# 7_Mosfets.net
KiCad netlist of a schematic drawn in Altium Designer
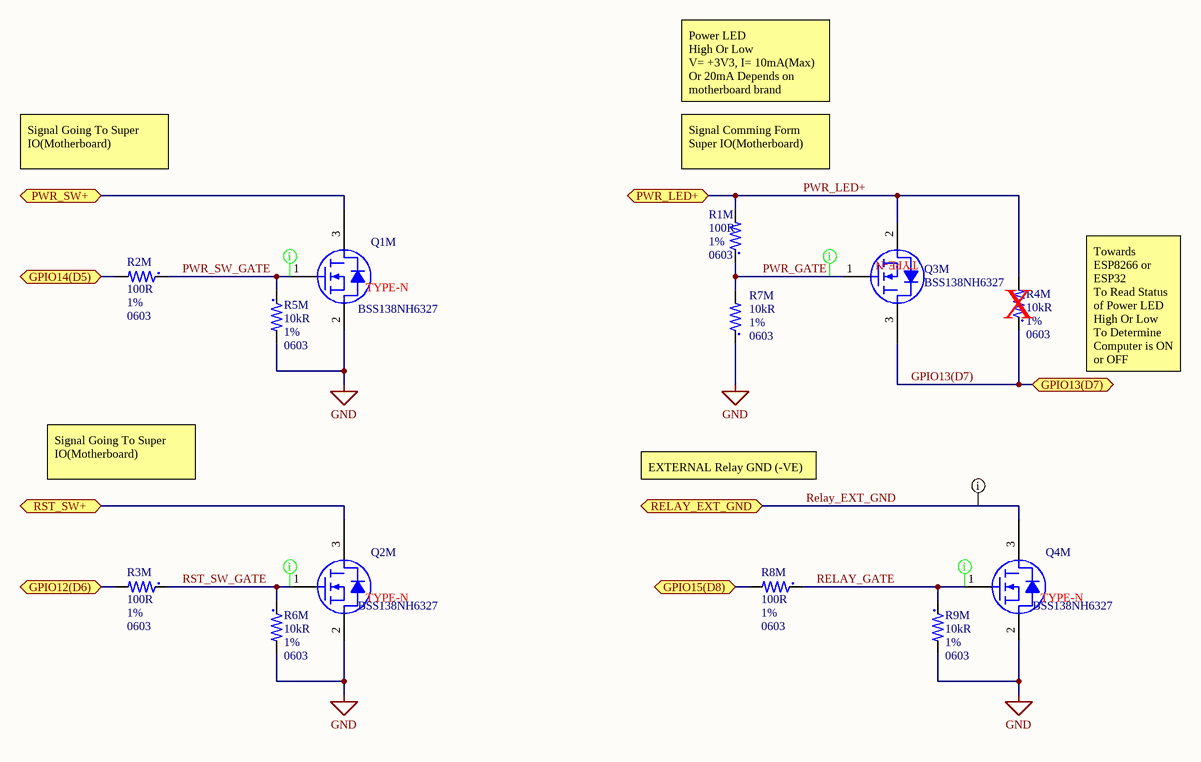
[diagram p0: 7_Mosfets.SchDoc]

(export (version "E")
  (design (tool "Eeschema 10.0.6"))
  (components
    (comp (ref "Q1M")
      (value "BSS138NH6327")
      (footprint "SOT-23-3-IPC_C")
      (description "Single N-Channel 60 V 3.5 Ohm 1 nC SIPMOS® Small Signal Mosfet - SOT-23")
      (fields (field (name "MANUFACTURER") "Infineon") (field (name "VOLTAGE") "50V"))
      (libsource (lib "") (part "BSS138NH6327_1"))
    )
    (comp (ref "Q2M")
      (value "BSS138NH6327")
      (footprint "SOT-23-3-IPC_C")
      (description "Single N-Channel 60 V 3.5 Ohm 1 nC SIPMOS® Small Signal Mosfet - SOT-23")
      (fields (field (name "MANUFACTURER") "Infineon") (field (name "VOLTAGE") "50V"))
      (libsource (lib "") (part "BSS138NH6327_1"))
    )
    (comp (ref "Q3M")
      (value "BSS138NH6327")
      (footprint "SOT-23-3-IPC_C")
      (description "Single N-Channel 60 V 3.5 Ohm 1 nC SIPMOS® Small Signal Mosfet - SOT-23")
      (fields (field (name "MANUFACTURER") "Infineon") (field (name "VOLTAGE") "50V"))
      (libsource (lib "Lib_Mosfet_NPN") (part "BSS138NH6327"))
    )
    (comp (ref "Q4M")
      (value "BSS138NH6327")
      (footprint "SOT-23-3-IPC_C")
      (description "Single N-Channel 60 V 3.5 Ohm 1 nC SIPMOS® Small Signal Mosfet - SOT-23")
      (fields (field (name "MANUFACTURER") "Infineon") (field (name "VOLTAGE") "50V"))
      (libsource (lib "") (part "BSS138NH6327_1"))
    )
    (comp (ref "R1M")
      (value "100R")
      (footprint "R0603-MFG")
      (description "SMD Chip Resistor, 100 Ohm, ± 1%, 100 mW, 0603 [1608 Metric], Thick Film, General Purpose")
      (fields
        (field (name "MANUFACTURER") "Yageo")
        (field (name "MANUFACTURER PART NUMBER") "AC0603FR-07100RL")
        (field (name "TOLERANCE") "1%")
        (field (name "CASE/PACKAGE") "0603")
      )
      (libsource (lib "Lib_Register_0603") (part "100R"))
    )
    (comp (ref "R2M")
      (value "100R")
      (footprint "R0603-MFG")
      (description "SMD Chip Resistor, 100 Ohm, ± 1%, 100 mW, 0603 [1608 Metric], Thick Film, General Purpose")
      (fields
        (field (name "MANUFACTURER") "Yageo")
        (field (name "MANUFACTURER PART NUMBER") "AC0603FR-07100RL")
        (field (name "TOLERANCE") "1%")
        (field (name "CASE/PACKAGE") "0603")
      )
      (libsource (lib "Lib_Register_0603") (part "100R"))
    )
    (comp (ref "R3M")
      (value "100R")
      (footprint "R0603-MFG")
      (description "SMD Chip Resistor, 100 Ohm, ± 1%, 100 mW, 0603 [1608 Metric], Thick Film, General Purpose")
      (fields
        (field (name "MANUFACTURER") "Yageo")
        (field (name "MANUFACTURER PART NUMBER") "AC0603FR-07100RL")
        (field (name "TOLERANCE") "1%")
        (field (name "CASE/PACKAGE") "0603")
      )
      (libsource (lib "Lib_Register_0603") (part "100R"))
    )
    (comp (ref "R4M")
      (value "10kR")
      (footprint "R0603-MFG")
      (description "SMD Chip Resistor, 10 kOhm, ± 1%, 100 mW, 0603 [1608 Metric], Thick Film, General Purpose")
      (fields
        (field (name "MANUFACTURER") "Yageo")
        (field (name "MANUFACTURER PART NUMBER") "RC0603FR-0710KL")
        (field (name "TOLERANCE") "1%")
        (field (name "CASE/PACKAGE") "0603")
      )
      (libsource (lib "Lib_Register_0603") (part "10K"))
    )
    (comp (ref "R5M")
      (value "10kR")
      (footprint "R0603-MFG")
      (description "SMD Chip Resistor, 10 kOhm, ± 1%, 100 mW, 0603 [1608 Metric], Thick Film, General Purpose")
      (fields
        (field (name "MANUFACTURER") "Yageo")
        (field (name "MANUFACTURER PART NUMBER") "RC0603FR-0710KL")
        (field (name "TOLERANCE") "1%")
        (field (name "CASE/PACKAGE") "0603")
      )
      (libsource (lib "Lib_Register_0603") (part "10K"))
    )
    (comp (ref "R6M")
      (value "10kR")
      (footprint "R0603-MFG")
      (description "SMD Chip Resistor, 10 kOhm, ± 1%, 100 mW, 0603 [1608 Metric], Thick Film, General Purpose")
      (fields
        (field (name "MANUFACTURER") "Yageo")
        (field (name "MANUFACTURER PART NUMBER") "RC0603FR-0710KL")
        (field (name "TOLERANCE") "1%")
        (field (name "CASE/PACKAGE") "0603")
      )
      (libsource (lib "Lib_Register_0603") (part "10K"))
    )
    (comp (ref "R7M")
      (value "10kR")
      (footprint "R0603-MFG")
      (description "SMD Chip Resistor, 10 kOhm, ± 1%, 100 mW, 0603 [1608 Metric], Thick Film, General Purpose")
      (fields
        (field (name "MANUFACTURER") "Yageo")
        (field (name "MANUFACTURER PART NUMBER") "RC0603FR-0710KL")
        (field (name "TOLERANCE") "1%")
        (field (name "CASE/PACKAGE") "0603")
      )
      (libsource (lib "Lib_Register_0603") (part "10K"))
    )
    (comp (ref "R8M")
      (value "100R")
      (footprint "R0603-MFG")
      (description "SMD Chip Resistor, 100 Ohm, ± 1%, 100 mW, 0603 [1608 Metric], Thick Film, General Purpose")
      (fields
        (field (name "MANUFACTURER") "Yageo")
        (field (name "MANUFACTURER PART NUMBER") "AC0603FR-07100RL")
        (field (name "TOLERANCE") "1%")
        (field (name "CASE/PACKAGE") "0603")
      )
      (libsource (lib "Lib_Register_0603") (part "100R"))
    )
    (comp (ref "R9M")
      (value "10kR")
      (footprint "R0603-MFG")
      (description "SMD Chip Resistor, 10 kOhm, ± 1%, 100 mW, 0603 [1608 Metric], Thick Film, General Purpose")
      (fields
        (field (name "MANUFACTURER") "Yageo")
        (field (name "MANUFACTURER PART NUMBER") "RC0603FR-0710KL")
        (field (name "TOLERANCE") "1%")
        (field (name "CASE/PACKAGE") "0603")
      )
      (libsource (lib "Lib_Register_0603") (part "10K"))
    )
  )
  (nets
    (net (code "1") (name "/GPIO12(D6)") (class "Default")
      (node (ref "R3M") (pin "2") (pinfunction "2_2") (pintype "passive"))
    )
    (net (code "2") (name "/GPIO13(D7)") (class "Default")
      (node (ref "Q3M") (pin "3") (pinfunction "D_3") (pintype "passive"))
      (node (ref "R4M") (pin "1") (pinfunction "1_1") (pintype "passive"))
    )
    (net (code "3") (name "/GPIO14(D5)") (class "Default")
      (node (ref "R2M") (pin "2") (pinfunction "2_2") (pintype "passive"))
    )
    (net (code "4") (name "/GPIO15(D8)") (class "Default")
      (node (ref "R8M") (pin "2") (pinfunction "2_2") (pintype "passive"))
    )
    (net (code "5") (name "/PWR_GATE") (class "Default")
      (node (ref "Q3M") (pin "1") (pinfunction "G_1") (pintype "passive"))
      (node (ref "R1M") (pin "1") (pinfunction "1_1") (pintype "passive"))
      (node (ref "R7M") (pin "2") (pinfunction "2_2") (pintype "passive"))
    )
    (net (code "6") (name "/PWR_LED+") (class "Default")
      (node (ref "Q3M") (pin "2") (pinfunction "S_2") (pintype "passive"))
      (node (ref "R1M") (pin "2") (pinfunction "2_2") (pintype "passive"))
      (node (ref "R4M") (pin "2") (pinfunction "2_2") (pintype "passive"))
    )
    (net (code "7") (name "/PWR_SW+") (class "Default")
      (node (ref "Q1M") (pin "3") (pinfunction "D_3") (pintype "passive"))
    )
    (net (code "8") (name "/PWR_SW_GATE") (class "Default")
      (node (ref "Q1M") (pin "1") (pinfunction "G_1") (pintype "passive"))
      (node (ref "R2M") (pin "1") (pinfunction "1_1") (pintype "passive"))
      (node (ref "R5M") (pin "1") (pinfunction "1_1") (pintype "passive"))
    )
    (net (code "9") (name "/RELAY_GATE") (class "Default")
      (node (ref "Q4M") (pin "1") (pinfunction "G_1") (pintype "passive"))
      (node (ref "R8M") (pin "1") (pinfunction "1_1") (pintype "passive"))
      (node (ref "R9M") (pin "1") (pinfunction "1_1") (pintype "passive"))
    )
    (net (code "10") (name "/RST_SW+") (class "Default")
      (node (ref "Q2M") (pin "3") (pinfunction "D_3") (pintype "passive"))
    )
    (net (code "11") (name "/RST_SW_GATE") (class "Default")
      (node (ref "Q2M") (pin "1") (pinfunction "G_1") (pintype "passive"))
      (node (ref "R3M") (pin "1") (pinfunction "1_1") (pintype "passive"))
      (node (ref "R6M") (pin "1") (pinfunction "1_1") (pintype "passive"))
    )
    (net (code "12") (name "/Relay_EXT_GND") (class "Default")
      (node (ref "Q4M") (pin "3") (pinfunction "D_3") (pintype "passive"))
    )
    (net (code "13") (name "GND") (class "Default")
      (node (ref "Q1M") (pin "2") (pinfunction "S_2") (pintype "passive"))
      (node (ref "Q2M") (pin "2") (pinfunction "S_2") (pintype "passive"))
      (node (ref "Q4M") (pin "2") (pinfunction "S_2") (pintype "passive"))
      (node (ref "R5M") (pin "2") (pinfunction "2_2") (pintype "passive"))
      (node (ref "R6M") (pin "2") (pinfunction "2_2") (pintype "passive"))
      (node (ref "R7M") (pin "1") (pinfunction "1_1") (pintype "passive"))
      (node (ref "R9M") (pin "2") (pinfunction "2_2") (pintype "passive"))
    )
  )
)
